# PCM1794_DAC_Test_V1.net
KiCad netlist of a schematic drawn in EAGLE
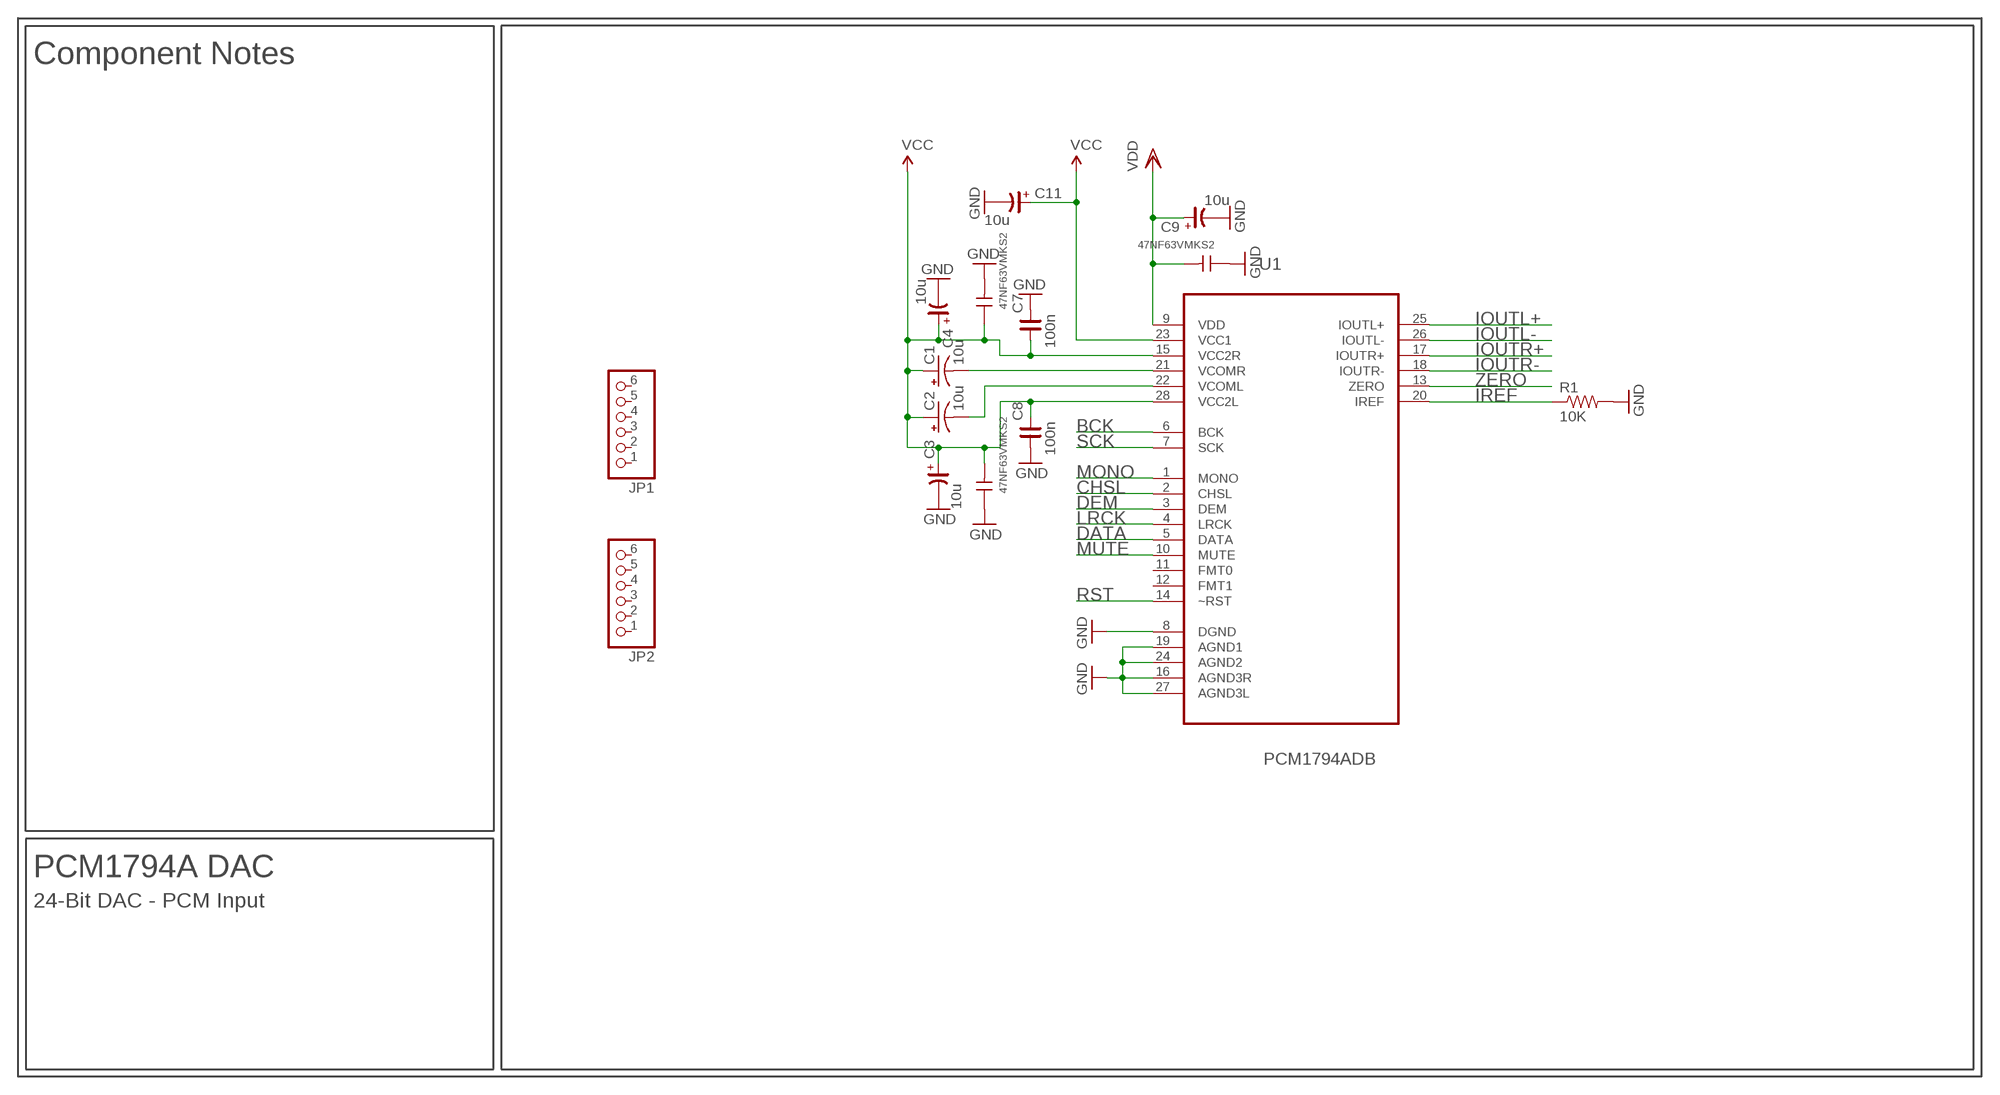
[diagram p0: schematic, sheet 1]
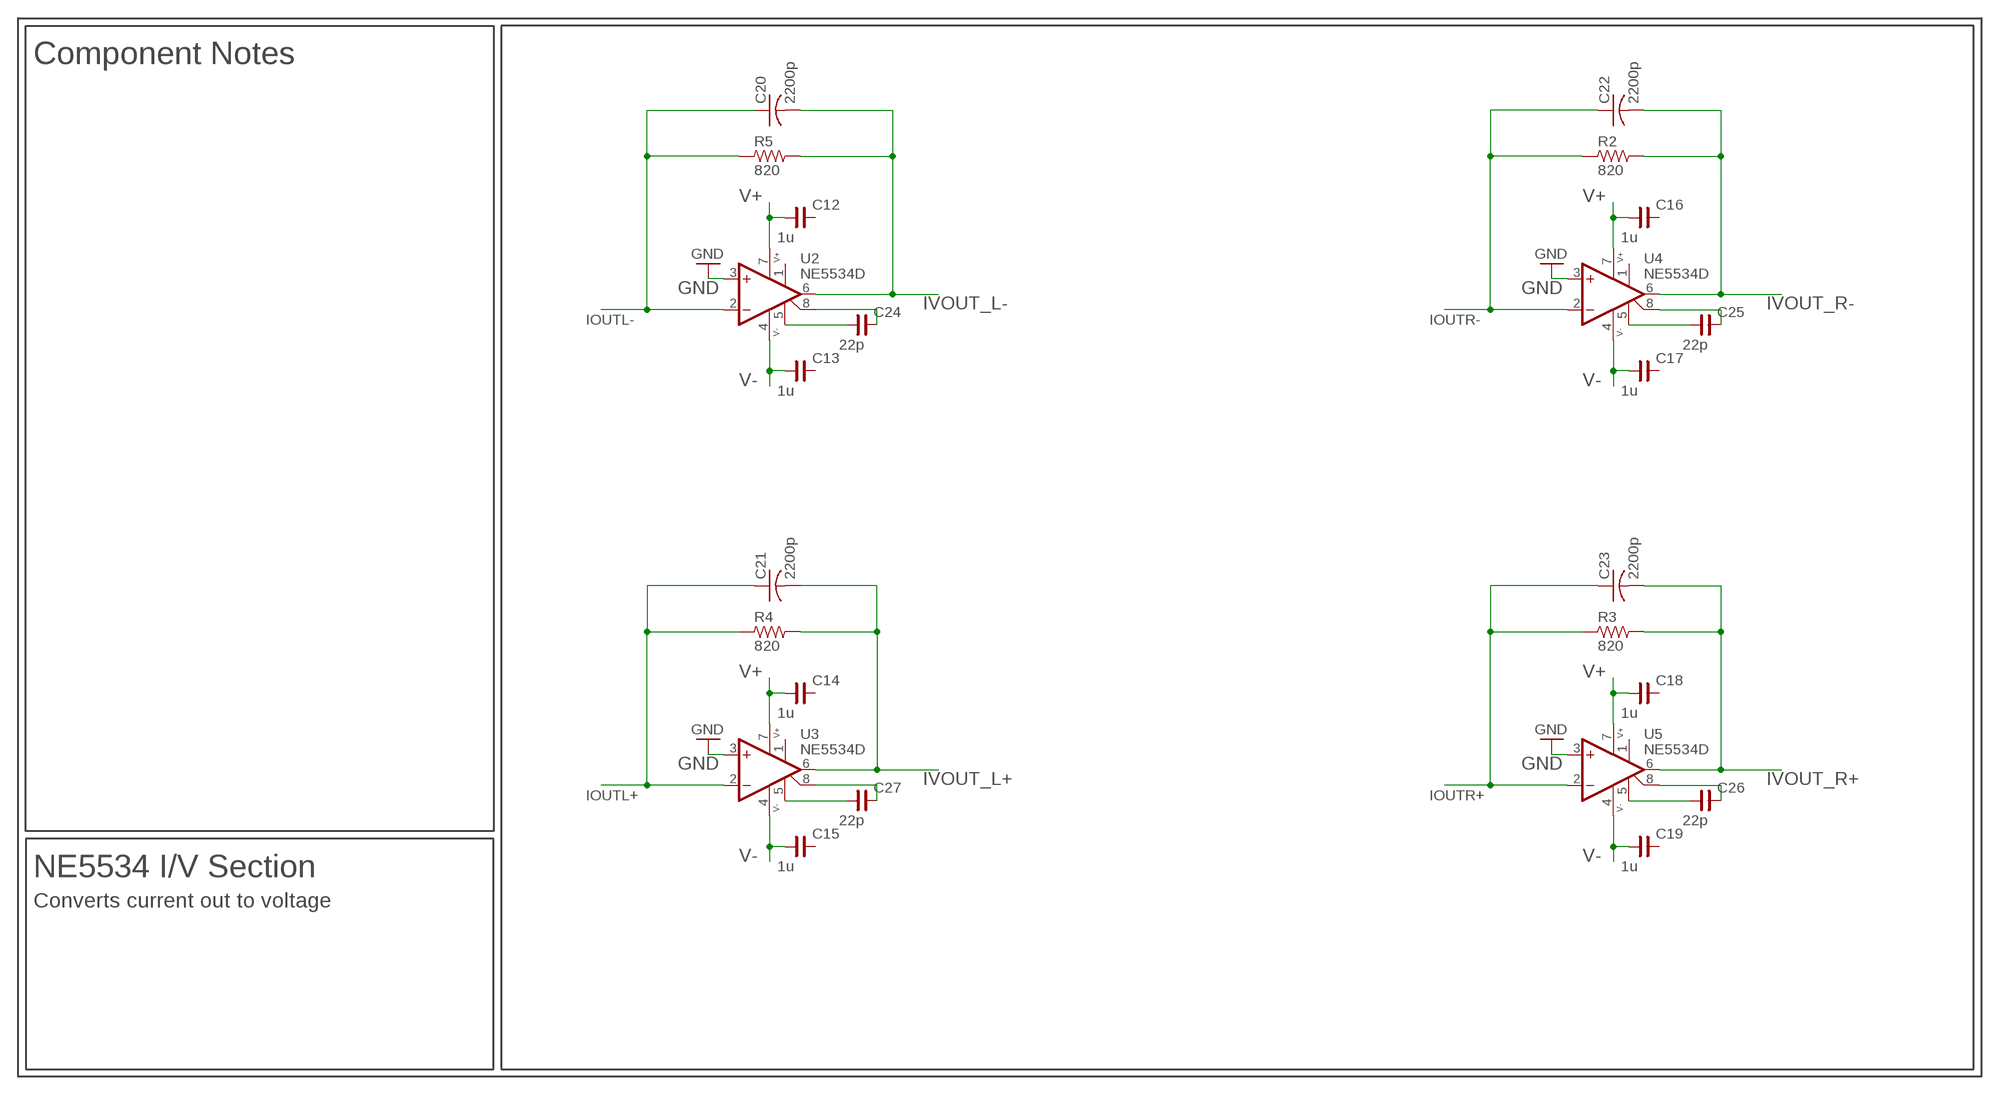
[diagram p1: schematic, sheet 2]
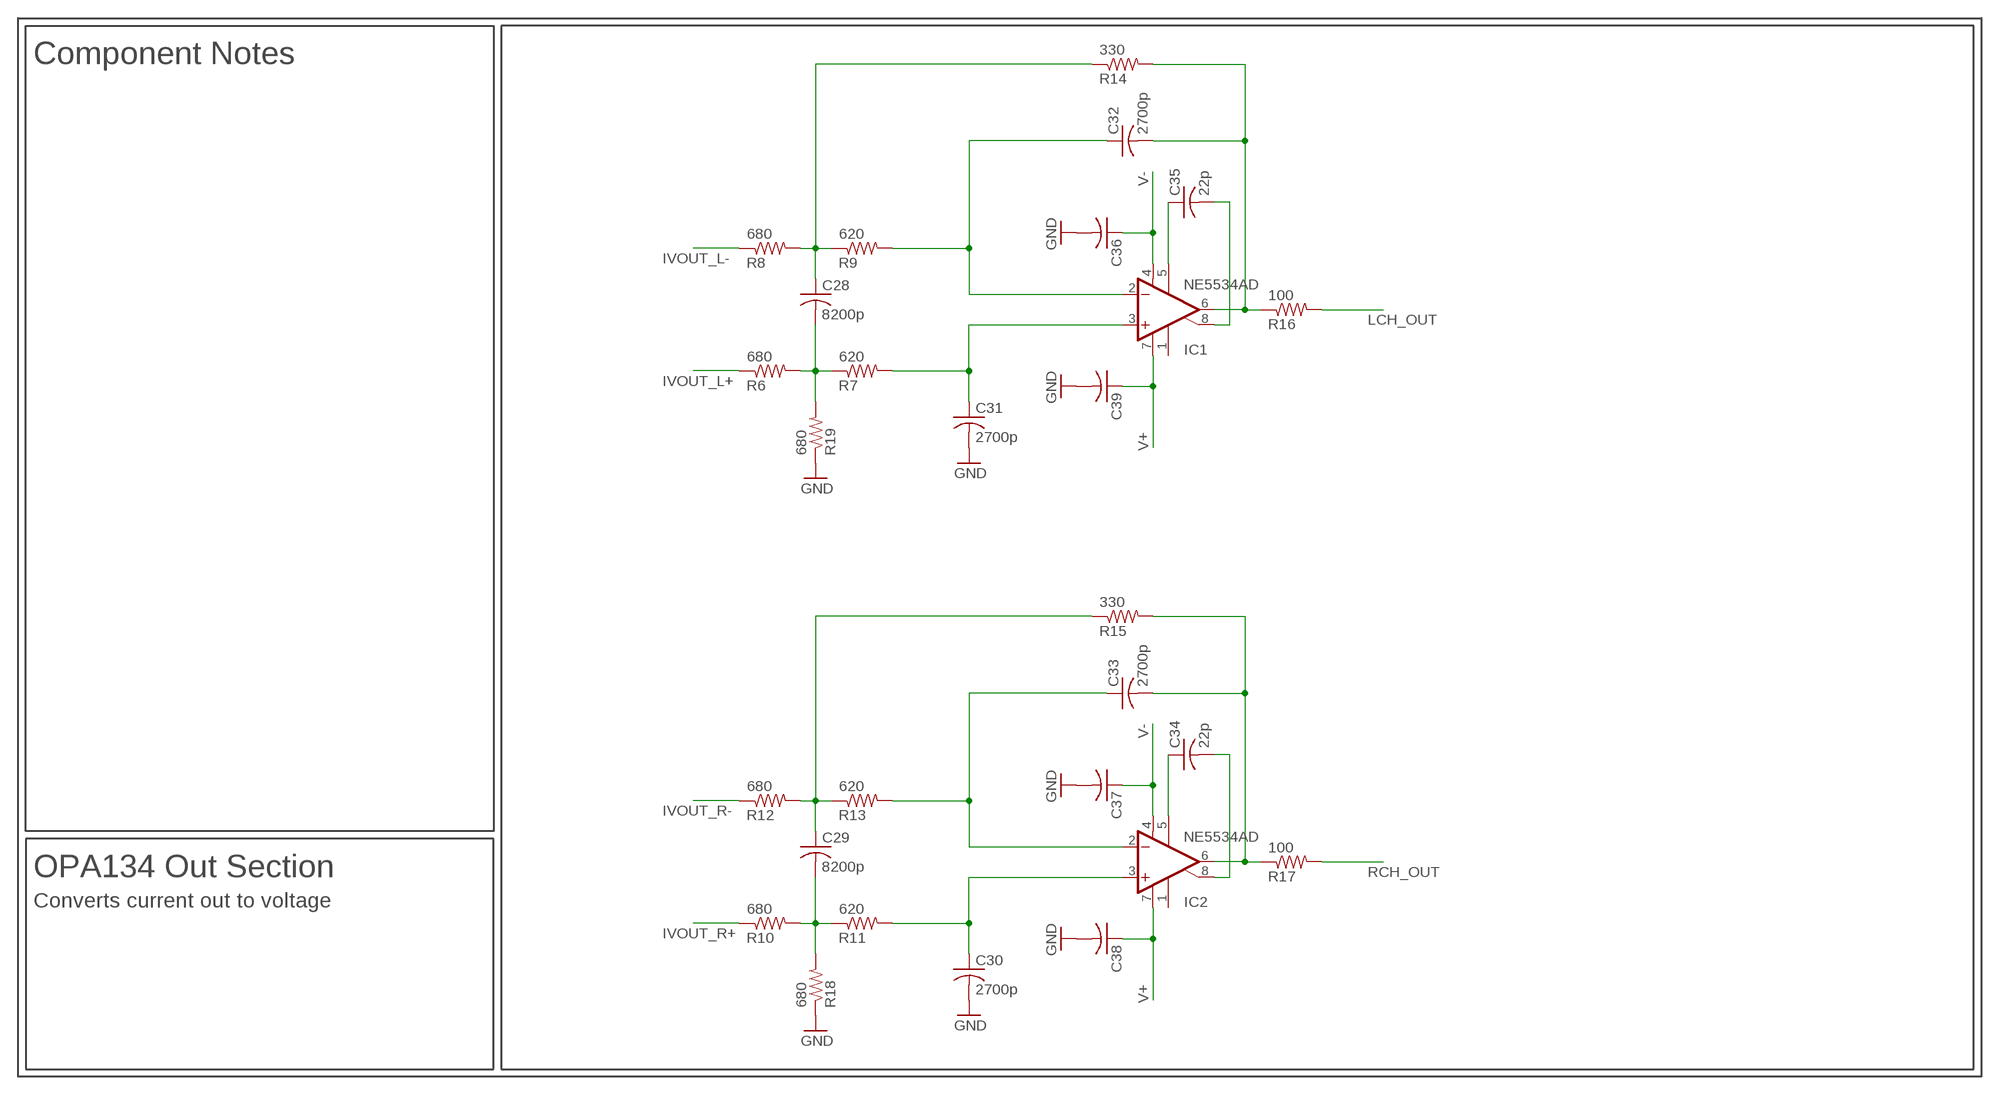
[diagram p2: schematic, sheet 3]

(export (version "E")
  (design (tool "Eeschema 10.0.6"))
  (components
    (comp (ref "C12")
      (value "1u")
      (footprint "eagle-import:C0603")
      (libsource (lib "eagle-import") (part "C_0603"))
    )
    (comp (ref "C13")
      (value "1u")
      (footprint "eagle-import:C0603")
      (libsource (lib "eagle-import") (part "C_0603"))
    )
    (comp (ref "C14")
      (value "1u")
      (footprint "eagle-import:C0603")
      (libsource (lib "eagle-import") (part "C_0603"))
    )
    (comp (ref "C15")
      (value "1u")
      (footprint "eagle-import:C0603")
      (libsource (lib "eagle-import") (part "C_0603"))
    )
    (comp (ref "C16")
      (value "1u")
      (footprint "eagle-import:C0603")
      (libsource (lib "eagle-import") (part "C_0603"))
    )
    (comp (ref "C17")
      (value "1u")
      (footprint "eagle-import:C0603")
      (libsource (lib "eagle-import") (part "C_0603"))
    )
    (comp (ref "C18")
      (value "1u")
      (footprint "eagle-import:C0603")
      (libsource (lib "eagle-import") (part "C_0603"))
    )
    (comp (ref "C19")
      (value "1u")
      (footprint "eagle-import:C0603")
      (libsource (lib "eagle-import") (part "C_0603"))
    )
    (comp (ref "C20")
      (value "2200p")
      (footprint "eagle-import:C0805")
      (libsource (lib "eagle-import") (part "C-USC0805"))
    )
    (comp (ref "C21")
      (value "2200p")
      (footprint "eagle-import:C0805")
      (libsource (lib "eagle-import") (part "C-USC0805"))
    )
    (comp (ref "C22")
      (value "2200p")
      (footprint "eagle-import:C0805")
      (libsource (lib "eagle-import") (part "C-USC0805"))
    )
    (comp (ref "C23")
      (value "2200p")
      (footprint "eagle-import:C0805")
      (libsource (lib "eagle-import") (part "C-USC0805"))
    )
    (comp (ref "C24")
      (value "22p")
      (footprint "eagle-import:C0603")
      (libsource (lib "eagle-import") (part "C_0603"))
    )
    (comp (ref "C25")
      (value "22p")
      (footprint "eagle-import:C0603")
      (libsource (lib "eagle-import") (part "C_0603"))
    )
    (comp (ref "C26")
      (value "22p")
      (footprint "eagle-import:C0603")
      (libsource (lib "eagle-import") (part "C_0603"))
    )
    (comp (ref "C27")
      (value "22p")
      (footprint "eagle-import:C0603")
      (libsource (lib "eagle-import") (part "C_0603"))
    )
    (comp (ref "R2")
      (value "820")
      (footprint "eagle-import:R0603")
      (libsource (lib "eagle-import") (part "R_0603"))
    )
    (comp (ref "R3")
      (value "820")
      (footprint "eagle-import:R0603")
      (libsource (lib "eagle-import") (part "R_0603"))
    )
    (comp (ref "R4")
      (value "820")
      (footprint "eagle-import:R0603")
      (libsource (lib "eagle-import") (part "R_0603"))
    )
    (comp (ref "R5")
      (value "820")
      (footprint "eagle-import:R0603")
      (libsource (lib "eagle-import") (part "R_0603"))
    )
    (comp (ref "U2")
      (value "NE5534D")
      (footprint "eagle-import:SO08")
      (libsource (lib "eagle-import") (part "op-amp_NE5534D"))
    )
    (comp (ref "U3")
      (value "NE5534D")
      (footprint "eagle-import:SO08")
      (libsource (lib "eagle-import") (part "op-amp_NE5534D"))
    )
    (comp (ref "U4")
      (value "NE5534D")
      (footprint "eagle-import:SO08")
      (libsource (lib "eagle-import") (part "op-amp_NE5534D"))
    )
    (comp (ref "U5")
      (value "NE5534D")
      (footprint "eagle-import:SO08")
      (libsource (lib "eagle-import") (part "op-amp_NE5534D"))
    )
    (comp (ref "C1")
      (value "10u")
      (footprint "eagle-import:PANASONIC_A")
      (libsource (lib "eagle-import") (part "CPOL-USA"))
    )
    (comp (ref "C2")
      (value "10u")
      (footprint "eagle-import:PANASONIC_A")
      (libsource (lib "eagle-import") (part "CPOL-USA"))
    )
    (comp (ref "C3")
      (value "10u")
      (footprint "eagle-import:CE-020X050")
      (libsource (lib "eagle-import") (part "CP_E-020X050"))
    )
    (comp (ref "C4")
      (value "10u")
      (footprint "eagle-import:CE-020X050")
      (libsource (lib "eagle-import") (part "CP_E-020X050"))
    )
    (comp (ref "C5")
      (value "47NF63VMKS2")
      (footprint "eagle-import:2,5X6,5RM5,0")
      (libsource (lib "eagle-import") (part "47NF63VMKS2"))
    )
    (comp (ref "C6")
      (value "47NF63VMKS2")
      (footprint "eagle-import:2,5X6,5RM5,0")
      (libsource (lib "eagle-import") (part "47NF63VMKS2"))
    )
    (comp (ref "C7")
      (value "100n")
      (footprint "eagle-import:C0603")
      (libsource (lib "eagle-import") (part "C_0603"))
    )
    (comp (ref "C8")
      (value "100n")
      (footprint "eagle-import:C0603")
      (libsource (lib "eagle-import") (part "C_0603"))
    )
    (comp (ref "C9")
      (value "10u")
      (footprint "eagle-import:CE-020X050")
      (libsource (lib "eagle-import") (part "CP_E-020X050"))
    )
    (comp (ref "C10")
      (value "47NF63VMKS2")
      (footprint "eagle-import:2,5X6,5RM5,0")
      (libsource (lib "eagle-import") (part "47NF63VMKS2"))
    )
    (comp (ref "C11")
      (value "10u")
      (footprint "eagle-import:CE-020X050")
      (libsource (lib "eagle-import") (part "CP_E-020X050"))
    )
    (comp (ref "JP1")
      (value "PINHD-1X6")
      (footprint "eagle-import:1X06")
      (libsource (lib "eagle-import") (part "PINHD-1X6"))
    )
    (comp (ref "JP2")
      (value "PINHD-1X6")
      (footprint "eagle-import:1X06")
      (libsource (lib "eagle-import") (part "PINHD-1X6"))
    )
    (comp (ref "R1")
      (value "10K")
      (footprint "eagle-import:R0603")
      (libsource (lib "eagle-import") (part "R-US_R0603"))
    )
    (comp (ref "U1")
      (value "PCM1794ADB")
      (footprint "eagle-import:SOP65P780X200-28N")
      (libsource (lib "eagle-import") (part "PCM1794ADB"))
    )
    (comp (ref "C28")
      (value "8200p")
      (footprint "eagle-import:C0805")
      (libsource (lib "eagle-import") (part "C-USC0805"))
    )
    (comp (ref "C29")
      (value "8200p")
      (footprint "eagle-import:C0805")
      (libsource (lib "eagle-import") (part "C-USC0805"))
    )
    (comp (ref "C30")
      (value "2700p")
      (footprint "eagle-import:C0805")
      (libsource (lib "eagle-import") (part "C-USC0805"))
    )
    (comp (ref "C31")
      (value "2700p")
      (footprint "eagle-import:C0805")
      (libsource (lib "eagle-import") (part "C-USC0805"))
    )
    (comp (ref "C32")
      (value "2700p")
      (footprint "eagle-import:C0805")
      (libsource (lib "eagle-import") (part "C-USC0805"))
    )
    (comp (ref "C33")
      (value "2700p")
      (footprint "eagle-import:C0805")
      (libsource (lib "eagle-import") (part "C-USC0805"))
    )
    (comp (ref "C34")
      (value "22p")
      (footprint "eagle-import:C0603")
      (libsource (lib "eagle-import") (part "C-USC0603"))
    )
    (comp (ref "C35")
      (value "22p")
      (footprint "eagle-import:C0603")
      (libsource (lib "eagle-import") (part "C-USC0603"))
    )
    (comp (ref "C36")
      (value "C-USC0603")
      (footprint "eagle-import:C0603")
      (libsource (lib "eagle-import") (part "C-USC0603"))
    )
    (comp (ref "C37")
      (value "C-USC0603")
      (footprint "eagle-import:C0603")
      (libsource (lib "eagle-import") (part "C-USC0603"))
    )
    (comp (ref "C38")
      (value "C-USC0603")
      (footprint "eagle-import:C0603")
      (libsource (lib "eagle-import") (part "C-USC0603"))
    )
    (comp (ref "C39")
      (value "C-USC0603")
      (footprint "eagle-import:C0603")
      (libsource (lib "eagle-import") (part "C-USC0603"))
    )
    (comp (ref "IC1")
      (value "NE5534AD")
      (footprint "eagle-import:SO08")
      (libsource (lib "eagle-import") (part "NE5534DA"))
    )
    (comp (ref "IC2")
      (value "NE5534AD")
      (footprint "eagle-import:SO08")
      (libsource (lib "eagle-import") (part "NE5534DA"))
    )
    (comp (ref "R6")
      (value "680")
      (footprint "eagle-import:R0805")
      (libsource (lib "eagle-import") (part "R-US_R0805"))
    )
    (comp (ref "R7")
      (value "620")
      (footprint "eagle-import:R0805")
      (libsource (lib "eagle-import") (part "R-US_R0805"))
    )
    (comp (ref "R8")
      (value "680")
      (footprint "eagle-import:R0805")
      (libsource (lib "eagle-import") (part "R-US_R0805"))
    )
    (comp (ref "R9")
      (value "620")
      (footprint "eagle-import:R0805")
      (libsource (lib "eagle-import") (part "R-US_R0805"))
    )
    (comp (ref "R10")
      (value "680")
      (footprint "eagle-import:R0805")
      (libsource (lib "eagle-import") (part "R-US_R0805"))
    )
    (comp (ref "R11")
      (value "620")
      (footprint "eagle-import:R0805")
      (libsource (lib "eagle-import") (part "R-US_R0805"))
    )
    (comp (ref "R12")
      (value "680")
      (footprint "eagle-import:R0805")
      (libsource (lib "eagle-import") (part "R-US_R0805"))
    )
    (comp (ref "R13")
      (value "620")
      (footprint "eagle-import:R0805")
      (libsource (lib "eagle-import") (part "R-US_R0805"))
    )
    (comp (ref "R14")
      (value "330")
      (footprint "eagle-import:R0805")
      (libsource (lib "eagle-import") (part "R-US_R0805"))
    )
    (comp (ref "R15")
      (value "330")
      (footprint "eagle-import:R0805")
      (libsource (lib "eagle-import") (part "R-US_R0805"))
    )
    (comp (ref "R16")
      (value "100")
      (footprint "eagle-import:R0805")
      (libsource (lib "eagle-import") (part "R-US_R0805"))
    )
    (comp (ref "R17")
      (value "100")
      (footprint "eagle-import:R0805")
      (libsource (lib "eagle-import") (part "R-US_R0805"))
    )
    (comp (ref "R18")
      (value "680")
      (footprint "eagle-import:R0805")
      (libsource (lib "eagle-import") (part "R-US_R0805"))
    )
    (comp (ref "R19")
      (value "680")
      (footprint "eagle-import:R0805")
      (libsource (lib "eagle-import") (part "R-US_R0805"))
    )
  )
  (nets
    (net (code "1") (name "BCK") (class "Default")
      (node (ref "U1") (pin "6") (pinfunction "BCK_6") (pintype "input"))
    )
    (net (code "2") (name "CHSL") (class "Default")
      (node (ref "U1") (pin "2") (pinfunction "CHSL_2") (pintype "input"))
    )
    (net (code "3") (name "DATA") (class "Default")
      (node (ref "U1") (pin "5") (pinfunction "DATA_5") (pintype "input"))
    )
    (net (code "4") (name "DEM") (class "Default")
      (node (ref "U1") (pin "3") (pinfunction "DEM_3") (pintype "input"))
    )
    (net (code "5") (name "GND") (class "Default")
      (node (ref "C10") (pin "1") (pinfunction "1_1") (pintype "passive"))
      (node (ref "C11") (pin "-") (pinfunction "-_-") (pintype "passive"))
      (node (ref "C3") (pin "-") (pinfunction "-_-") (pintype "passive"))
      (node (ref "C30") (pin "2") (pinfunction "2_2") (pintype "passive"))
      (node (ref "C31") (pin "2") (pinfunction "2_2") (pintype "passive"))
      (node (ref "C36") (pin "2") (pinfunction "2_2") (pintype "passive"))
      (node (ref "C37") (pin "2") (pinfunction "2_2") (pintype "passive"))
      (node (ref "C38") (pin "2") (pinfunction "2_2") (pintype "passive"))
      (node (ref "C39") (pin "2") (pinfunction "2_2") (pintype "passive"))
      (node (ref "C4") (pin "-") (pinfunction "-_-") (pintype "passive"))
      (node (ref "C5") (pin "2") (pinfunction "2_2") (pintype "passive"))
      (node (ref "C6") (pin "1") (pinfunction "1_1") (pintype "passive"))
      (node (ref "C7") (pin "2") (pinfunction "2_2") (pintype "passive"))
      (node (ref "C8") (pin "1") (pinfunction "1_1") (pintype "passive"))
      (node (ref "C9") (pin "-") (pinfunction "-_-") (pintype "passive"))
      (node (ref "R1") (pin "2") (pinfunction "2_2") (pintype "passive"))
      (node (ref "R18") (pin "1") (pinfunction "1_1") (pintype "passive"))
      (node (ref "R19") (pin "1") (pinfunction "1_1") (pintype "passive"))
      (node (ref "U1") (pin "16") (pinfunction "AGND3R_16") (pintype "passive"))
      (node (ref "U1") (pin "19") (pinfunction "AGND1_19") (pintype "passive"))
      (node (ref "U1") (pin "24") (pinfunction "AGND2_24") (pintype "passive"))
      (node (ref "U1") (pin "27") (pinfunction "AGND3L_27") (pintype "passive"))
      (node (ref "U1") (pin "8") (pinfunction "DGND_8") (pintype "passive"))
      (node (ref "U2") (pin "3") (pinfunction "+IN_3") (pintype "input"))
      (node (ref "U3") (pin "3") (pinfunction "+IN_3") (pintype "input"))
      (node (ref "U4") (pin "3") (pinfunction "+IN_3") (pintype "input"))
      (node (ref "U5") (pin "3") (pinfunction "+IN_3") (pintype "input"))
    )
    (net (code "6") (name "IOUTL+") (class "Default")
      (node (ref "C21") (pin "1") (pinfunction "1_1") (pintype "passive"))
      (node (ref "R4") (pin "1") (pinfunction "1_1") (pintype "passive"))
      (node (ref "U1") (pin "25") (pinfunction "IOUTL+_25") (pintype "output"))
      (node (ref "U3") (pin "2") (pinfunction "-IN_2") (pintype "input"))
    )
    (net (code "7") (name "IOUTL-") (class "Default")
      (node (ref "C20") (pin "1") (pinfunction "1_1") (pintype "passive"))
      (node (ref "R5") (pin "1") (pinfunction "1_1") (pintype "passive"))
      (node (ref "U1") (pin "26") (pinfunction "IOUTL-_26") (pintype "output"))
      (node (ref "U2") (pin "2") (pinfunction "-IN_2") (pintype "input"))
    )
    (net (code "8") (name "IOUTR+") (class "Default")
      (node (ref "C23") (pin "1") (pinfunction "1_1") (pintype "passive"))
      (node (ref "R3") (pin "1") (pinfunction "1_1") (pintype "passive"))
      (node (ref "U1") (pin "17") (pinfunction "IOUTR+_17") (pintype "output"))
      (node (ref "U5") (pin "2") (pinfunction "-IN_2") (pintype "input"))
    )
    (net (code "9") (name "IOUTR-") (class "Default")
      (node (ref "C22") (pin "1") (pinfunction "1_1") (pintype "passive"))
      (node (ref "R2") (pin "1") (pinfunction "1_1") (pintype "passive"))
      (node (ref "U1") (pin "18") (pinfunction "IOUTR-_18") (pintype "output"))
      (node (ref "U4") (pin "2") (pinfunction "-IN_2") (pintype "input"))
    )
    (net (code "10") (name "IREF") (class "Default")
      (node (ref "R1") (pin "1") (pinfunction "1_1") (pintype "passive"))
      (node (ref "U1") (pin "20") (pinfunction "IREF_20") (pintype "output"))
    )
    (net (code "11") (name "IVOUT_L+") (class "Default")
      (node (ref "C21") (pin "2") (pinfunction "2_2") (pintype "passive"))
      (node (ref "R4") (pin "2") (pinfunction "2_2") (pintype "passive"))
      (node (ref "R6") (pin "1") (pinfunction "1_1") (pintype "passive"))
      (node (ref "U3") (pin "6") (pinfunction "OUT_6") (pintype "output"))
    )
    (net (code "12") (name "IVOUT_L-") (class "Default")
      (node (ref "C20") (pin "2") (pinfunction "2_2") (pintype "passive"))
      (node (ref "R5") (pin "2") (pinfunction "2_2") (pintype "passive"))
      (node (ref "R8") (pin "1") (pinfunction "1_1") (pintype "passive"))
      (node (ref "U2") (pin "6") (pinfunction "OUT_6") (pintype "output"))
    )
    (net (code "13") (name "IVOUT_R+") (class "Default")
      (node (ref "C23") (pin "2") (pinfunction "2_2") (pintype "passive"))
      (node (ref "R10") (pin "1") (pinfunction "1_1") (pintype "passive"))
      (node (ref "R3") (pin "2") (pinfunction "2_2") (pintype "passive"))
      (node (ref "U5") (pin "6") (pinfunction "OUT_6") (pintype "output"))
    )
    (net (code "14") (name "IVOUT_R-") (class "Default")
      (node (ref "C22") (pin "2") (pinfunction "2_2") (pintype "passive"))
      (node (ref "R12") (pin "1") (pinfunction "1_1") (pintype "passive"))
      (node (ref "R2") (pin "2") (pinfunction "2_2") (pintype "passive"))
      (node (ref "U4") (pin "6") (pinfunction "OUT_6") (pintype "output"))
    )
    (net (code "15") (name "LCH_OUT") (class "Default")
      (node (ref "R16") (pin "2") (pinfunction "2_2") (pintype "passive"))
    )
    (net (code "16") (name "LRCK") (class "Default")
      (node (ref "U1") (pin "4") (pinfunction "LRCK_4") (pintype "input"))
    )
    (net (code "17") (name "MONO") (class "Default")
      (node (ref "U1") (pin "1") (pinfunction "MONO_1") (pintype "input"))
    )
    (net (code "18") (name "MUTE") (class "Default")
      (node (ref "U1") (pin "10") (pinfunction "MUTE_10") (pintype "input"))
    )
    (net (code "19") (name "Net-(C28-Pad1)") (class "Default")
      (node (ref "C28") (pin "1") (pinfunction "1_1") (pintype "passive"))
      (node (ref "R14") (pin "1") (pinfunction "1_1") (pintype "passive"))
      (node (ref "R8") (pin "2") (pinfunction "2_2") (pintype "passive"))
      (node (ref "R9") (pin "1") (pinfunction "1_1") (pintype "passive"))
    )
    (net (code "20") (name "Net-(C28-Pad2)") (class "Default")
      (node (ref "C28") (pin "2") (pinfunction "2_2") (pintype "passive"))
      (node (ref "R19") (pin "2") (pinfunction "2_2") (pintype "passive"))
      (node (ref "R6") (pin "2") (pinfunction "2_2") (pintype "passive"))
      (node (ref "R7") (pin "1") (pinfunction "1_1") (pintype "passive"))
    )
    (net (code "21") (name "Net-(C29-Pad1)") (class "Default")
      (node (ref "C29") (pin "1") (pinfunction "1_1") (pintype "passive"))
      (node (ref "R12") (pin "2") (pinfunction "2_2") (pintype "passive"))
      (node (ref "R13") (pin "1") (pinfunction "1_1") (pintype "passive"))
      (node (ref "R15") (pin "1") (pinfunction "1_1") (pintype "passive"))
    )
    (net (code "22") (name "Net-(C29-Pad2)") (class "Default")
      (node (ref "C29") (pin "2") (pinfunction "2_2") (pintype "passive"))
      (node (ref "R10") (pin "2") (pinfunction "2_2") (pintype "passive"))
      (node (ref "R11") (pin "1") (pinfunction "1_1") (pintype "passive"))
      (node (ref "R18") (pin "2") (pinfunction "2_2") (pintype "passive"))
    )
    (net (code "23") (name "Net-(IC1-+IN)") (class "Default")
      (node (ref "C31") (pin "1") (pinfunction "1_1") (pintype "passive"))
      (node (ref "IC1") (pin "3") (pinfunction "+IN_3") (pintype "input"))
      (node (ref "R7") (pin "2") (pinfunction "2_2") (pintype "passive"))
    )
    (net (code "24") (name "Net-(IC1--IN)") (class "Default")
      (node (ref "C32") (pin "1") (pinfunction "1_1") (pintype "passive"))
      (node (ref "IC1") (pin "2") (pinfunction "-IN_2") (pintype "input"))
      (node (ref "R9") (pin "2") (pinfunction "2_2") (pintype "passive"))
    )
    (net (code "25") (name "Net-(IC1-CMP)") (class "Default")
      (node (ref "C35") (pin "1") (pinfunction "1_1") (pintype "passive"))
      (node (ref "IC1") (pin "5") (pinfunction "CMP_5") (pintype "passive"))
    )
    (net (code "26") (name "Net-(IC1-ON{slash}CMP)") (class "Default")
      (node (ref "C35") (pin "2") (pinfunction "2_2") (pintype "passive"))
      (node (ref "IC1") (pin "8") (pinfunction "ON/CMP_8") (pintype "passive"))
    )
    (net (code "27") (name "Net-(IC1-OUT)") (class "Default")
      (node (ref "C32") (pin "2") (pinfunction "2_2") (pintype "passive"))
      (node (ref "IC1") (pin "6") (pinfunction "OUT_6") (pintype "output"))
      (node (ref "R14") (pin "2") (pinfunction "2_2") (pintype "passive"))
      (node (ref "R16") (pin "1") (pinfunction "1_1") (pintype "passive"))
    )
    (net (code "28") (name "Net-(IC2-+IN)") (class "Default")
      (node (ref "C30") (pin "1") (pinfunction "1_1") (pintype "passive"))
      (node (ref "IC2") (pin "3") (pinfunction "+IN_3") (pintype "input"))
      (node (ref "R11") (pin "2") (pinfunction "2_2") (pintype "passive"))
    )
    (net (code "29") (name "Net-(IC2--IN)") (class "Default")
      (node (ref "C33") (pin "1") (pinfunction "1_1") (pintype "passive"))
      (node (ref "IC2") (pin "2") (pinfunction "-IN_2") (pintype "input"))
      (node (ref "R13") (pin "2") (pinfunction "2_2") (pintype "passive"))
    )
    (net (code "30") (name "Net-(IC2-CMP)") (class "Default")
      (node (ref "C34") (pin "1") (pinfunction "1_1") (pintype "passive"))
      (node (ref "IC2") (pin "5") (pinfunction "CMP_5") (pintype "passive"))
    )
    (net (code "31") (name "Net-(IC2-ON{slash}CMP)") (class "Default")
      (node (ref "C34") (pin "2") (pinfunction "2_2") (pintype "passive"))
      (node (ref "IC2") (pin "8") (pinfunction "ON/CMP_8") (pintype "passive"))
    )
    (net (code "32") (name "Net-(IC2-OUT)") (class "Default")
      (node (ref "C33") (pin "2") (pinfunction "2_2") (pintype "passive"))
      (node (ref "IC2") (pin "6") (pinfunction "OUT_6") (pintype "output"))
      (node (ref "R15") (pin "2") (pinfunction "2_2") (pintype "passive"))
      (node (ref "R17") (pin "1") (pinfunction "1_1") (pintype "passive"))
    )
    (net (code "33") (name "Net-(U1-VCOML)") (class "Default")
      (node (ref "C2") (pin "-") (pinfunction "-_-") (pintype "passive"))
      (node (ref "U1") (pin "22") (pinfunction "VCOML_22") (pintype "input"))
    )
    (net (code "34") (name "Net-(U1-VCOMR)") (class "Default")
      (node (ref "C1") (pin "-") (pinfunction "-_-") (pintype "passive"))
      (node (ref "U1") (pin "21") (pinfunction "VCOMR_21") (pintype "input"))
    )
    (net (code "35") (name "Net-(U2B-BAL{slash}CMP)") (class "Default")
      (node (ref "C24") (pin "2") (pinfunction "2_2") (pintype "passive"))
      (node (ref "U2") (pin "8") (pinfunction "BAL/CMP_8") (pintype "passive"))
    )
    (net (code "36") (name "Net-(U2B-CMP)") (class "Default")
      (node (ref "C24") (pin "1") (pinfunction "1_1") (pintype "passive"))
      (node (ref "U2") (pin "5") (pinfunction "CMP_5") (pintype "passive"))
    )
    (net (code "37") (name "Net-(U3B-BAL{slash}CMP)") (class "Default")
      (node (ref "C27") (pin "2") (pinfunction "2_2") (pintype "passive"))
      (node (ref "U3") (pin "8") (pinfunction "BAL/CMP_8") (pintype "passive"))
    )
    (net (code "38") (name "Net-(U3B-CMP)") (class "Default")
      (node (ref "C27") (pin "1") (pinfunction "1_1") (pintype "passive"))
      (node (ref "U3") (pin "5") (pinfunction "CMP_5") (pintype "passive"))
    )
    (net (code "39") (name "Net-(U4B-BAL{slash}CMP)") (class "Default")
      (node (ref "C25") (pin "2") (pinfunction "2_2") (pintype "passive"))
      (node (ref "U4") (pin "8") (pinfunction "BAL/CMP_8") (pintype "passive"))
    )
    (net (code "40") (name "Net-(U4B-CMP)") (class "Default")
      (node (ref "C25") (pin "1") (pinfunction "1_1") (pintype "passive"))
      (node (ref "U4") (pin "5") (pinfunction "CMP_5") (pintype "passive"))
    )
    (net (code "41") (name "Net-(U5B-BAL{slash}CMP)") (class "Default")
      (node (ref "C26") (pin "2") (pinfunction "2_2") (pintype "passive"))
      (node (ref "U5") (pin "8") (pinfunction "BAL/CMP_8") (pintype "passive"))
    )
    (net (code "42") (name "Net-(U5B-CMP)") (class "Default")
      (node (ref "C26") (pin "1") (pinfunction "1_1") (pintype "passive"))
      (node (ref "U5") (pin "5") (pinfunction "CMP_5") (pintype "passive"))
    )
    (net (code "43") (name "RCH_OUT") (class "Default")
      (node (ref "R17") (pin "2") (pinfunction "2_2") (pintype "passive"))
    )
    (net (code "44") (name "RST") (class "Default")
      (node (ref "U1") (pin "14") (pinfunction "~{RST}_14") (pintype "input"))
    )
    (net (code "45") (name "SCK") (class "Default")
      (node (ref "U1") (pin "7") (pinfunction "SCK_7") (pintype "input"))
    )
    (net (code "46") (name "V+") (class "Default")
      (node (ref "C12") (pin "1") (pinfunction "1_1") (pintype "passive"))
      (node (ref "C14") (pin "1") (pinfunction "1_1") (pintype "passive"))
      (node (ref "C16") (pin "1") (pinfunction "1_1") (pintype "passive"))
      (node (ref "C18") (pin "1") (pinfunction "1_1") (pintype "passive"))
      (node (ref "C38") (pin "1") (pinfunction "1_1") (pintype "passive"))
      (node (ref "C39") (pin "1") (pinfunction "1_1") (pintype "passive"))
      (node (ref "IC1") (pin "7") (pinfunction "V+_7") (pintype "power_in"))
      (node (ref "IC2") (pin "7") (pinfunction "V+_7") (pintype "power_in"))
      (node (ref "U2") (pin "7") (pinfunction "V+_7") (pintype "power_in"))
      (node (ref "U3") (pin "7") (pinfunction "V+_7") (pintype "power_in"))
      (node (ref "U4") (pin "7") (pinfunction "V+_7") (pintype "power_in"))
      (node (ref "U5") (pin "7") (pinfunction "V+_7") (pintype "power_in"))
    )
    (net (code "47") (name "V-") (class "Default")
      (node (ref "C13") (pin "1") (pinfunction "1_1") (pintype "passive"))
      (node (ref "C15") (pin "1") (pinfunction "1_1") (pintype "passive"))
      (node (ref "C17") (pin "1") (pinfunction "1_1") (pintype "passive"))
      (node (ref "C19") (pin "1") (pinfunction "1_1") (pintype "passive"))
      (node (ref "C36") (pin "1") (pinfunction "1_1") (pintype "passive"))
      (node (ref "C37") (pin "1") (pinfunction "1_1") (pintype "passive"))
      (node (ref "IC1") (pin "4") (pinfunction "V-_4") (pintype "power_in"))
      (node (ref "IC2") (pin "4") (pinfunction "V-_4") (pintype "power_in"))
      (node (ref "U2") (pin "4") (pinfunction "V-_4") (pintype "power_in"))
      (node (ref "U3") (pin "4") (pinfunction "V-_4") (pintype "power_in"))
      (node (ref "U4") (pin "4") (pinfunction "V-_4") (pintype "power_in"))
      (node (ref "U5") (pin "4") (pinfunction "V-_4") (pintype "power_in"))
    )
    (net (code "48") (name "VCC") (class "Default")
      (node (ref "C1") (pin "+") (pinfunction "+_+") (pintype "passive"))
      (node (ref "C11") (pin "+") (pinfunction "+_+") (pintype "passive"))
      (node (ref "C2") (pin "+") (pinfunction "+_+") (pintype "passive"))
      (node (ref "C3") (pin "+") (pinfunction "+_+") (pintype "passive"))
      (node (ref "C4") (pin "+") (pinfunction "+_+") (pintype "passive"))
      (node (ref "C5") (pin "1") (pinfunction "1_1") (pintype "passive"))
      (node (ref "C6") (pin "2") (pinfunction "2_2") (pintype "passive"))
      (node (ref "C7") (pin "1") (pinfunction "1_1") (pintype "passive"))
      (node (ref "C8") (pin "2") (pinfunction "2_2") (pintype "passive"))
      (node (ref "U1") (pin "15") (pinfunction "VCC2R_15") (pintype "power_in"))
      (node (ref "U1") (pin "23") (pinfunction "VCC1_23") (pintype "power_in"))
      (node (ref "U1") (pin "28") (pinfunction "VCC2L_28") (pintype "power_in"))
    )
    (net (code "49") (name "VDD") (class "Default")
      (node (ref "C10") (pin "2") (pinfunction "2_2") (pintype "passive"))
      (node (ref "C9") (pin "+") (pinfunction "+_+") (pintype "passive"))
      (node (ref "U1") (pin "9") (pinfunction "VDD_9") (pintype "power_in"))
    )
    (net (code "50") (name "ZERO") (class "Default")
      (node (ref "U1") (pin "13") (pinfunction "ZERO_13") (pintype "output"))
    )
    (net (code "51") (name "unconnected-(C12-Pad2)") (class "Default")
      (node (ref "C12") (pin "2") (pinfunction "2_2") (pintype "passive"))
    )
    (net (code "52") (name "unconnected-(C13-Pad2)") (class "Default")
      (node (ref "C13") (pin "2") (pinfunction "2_2") (pintype "passive"))
    )
    (net (code "53") (name "unconnected-(C14-Pad2)") (class "Default")
      (node (ref "C14") (pin "2") (pinfunction "2_2") (pintype "passive"))
    )
    (net (code "54") (name "unconnected-(C15-Pad2)") (class "Default")
      (node (ref "C15") (pin "2") (pinfunction "2_2") (pintype "passive"))
    )
    (net (code "55") (name "unconnected-(C16-Pad2)") (class "Default")
      (node (ref "C16") (pin "2") (pinfunction "2_2") (pintype "passive"))
    )
    (net (code "56") (name "unconnected-(C17-Pad2)") (class "Default")
      (node (ref "C17") (pin "2") (pinfunction "2_2") (pintype "passive"))
    )
    (net (code "57") (name "unconnected-(C18-Pad2)") (class "Default")
      (node (ref "C18") (pin "2") (pinfunction "2_2") (pintype "passive"))
    )
    (net (code "58") (name "unconnected-(C19-Pad2)") (class "Default")
      (node (ref "C19") (pin "2") (pinfunction "2_2") (pintype "passive"))
    )
    (net (code "59") (name "unconnected-(IC1-ON-Pad1)") (class "Default")
      (node (ref "IC1") (pin "1") (pinfunction "ON_1") (pintype "passive"))
    )
    (net (code "60") (name "unconnected-(IC2-ON-Pad1)") (class "Default")
      (node (ref "IC2") (pin "1") (pinfunction "ON_1") (pintype "passive"))
    )
    (net (code "61") (name "unconnected-(JP1-Pad1)") (class "Default")
      (node (ref "JP1") (pin "1") (pinfunction "1_1") (pintype "passive"))
    )
    (net (code "62") (name "unconnected-(JP1-Pad2)") (class "Default")
      (node (ref "JP1") (pin "2") (pinfunction "2_2") (pintype "passive"))
    )
    (net (code "63") (name "unconnected-(JP1-Pad3)") (class "Default")
      (node (ref "JP1") (pin "3") (pinfunction "3_3") (pintype "passive"))
    )
    (net (code "64") (name "unconnected-(JP1-Pad4)") (class "Default")
      (node (ref "JP1") (pin "4") (pinfunction "4_4") (pintype "passive"))
    )
    (net (code "65") (name "unconnected-(JP1-Pad5)") (class "Default")
      (node (ref "JP1") (pin "5") (pinfunction "5_5") (pintype "passive"))
    )
    (net (code "66") (name "unconnected-(JP1-Pad6)") (class "Default")
      (node (ref "JP1") (pin "6") (pinfunction "6_6") (pintype "passive"))
    )
    (net (code "67") (name "unconnected-(JP2-Pad1)") (class "Default")
      (node (ref "JP2") (pin "1") (pinfunction "1_1") (pintype "passive"))
    )
    (net (code "68") (name "unconnected-(JP2-Pad2)") (class "Default")
      (node (ref "JP2") (pin "2") (pinfunction "2_2") (pintype "passive"))
    )
    (net (code "69") (name "unconnected-(JP2-Pad3)") (class "Default")
      (node (ref "JP2") (pin "3") (pinfunction "3_3") (pintype "passive"))
    )
    (net (code "70") (name "unconnected-(JP2-Pad4)") (class "Default")
      (node (ref "JP2") (pin "4") (pinfunction "4_4") (pintype "passive"))
    )
    (net (code "71") (name "unconnected-(JP2-Pad5)") (class "Default")
      (node (ref "JP2") (pin "5") (pinfunction "5_5") (pintype "passive"))
    )
    (net (code "72") (name "unconnected-(JP2-Pad6)") (class "Default")
      (node (ref "JP2") (pin "6") (pinfunction "6_6") (pintype "passive"))
    )
    (net (code "73") (name "unconnected-(U1-FMT0-Pad11)") (class "Default")
      (node (ref "U1") (pin "11") (pinfunction "FMT0_11") (pintype "input"))
    )
    (net (code "74") (name "unconnected-(U1-FMT1-Pad12)") (class "Default")
      (node (ref "U1") (pin "12") (pinfunction "FMT1_12") (pintype "input"))
    )
    (net (code "75") (name "unconnected-(U2A-BAL-Pad1)") (class "Default")
      (node (ref "U2") (pin "1") (pinfunction "BAL_1") (pintype "passive"))
    )
    (net (code "76") (name "unconnected-(U3A-BAL-Pad1)") (class "Default")
      (node (ref "U3") (pin "1") (pinfunction "BAL_1") (pintype "passive"))
    )
    (net (code "77") (name "unconnected-(U4A-BAL-Pad1)") (class "Default")
      (node (ref "U4") (pin "1") (pinfunction "BAL_1") (pintype "passive"))
    )
    (net (code "78") (name "unconnected-(U5A-BAL-Pad1)") (class "Default")
      (node (ref "U5") (pin "1") (pinfunction "BAL_1") (pintype "passive"))
    )
  )
)
